# Nano_C1101_ds.net
KiCad netlist of a schematic drawn in EAGLE
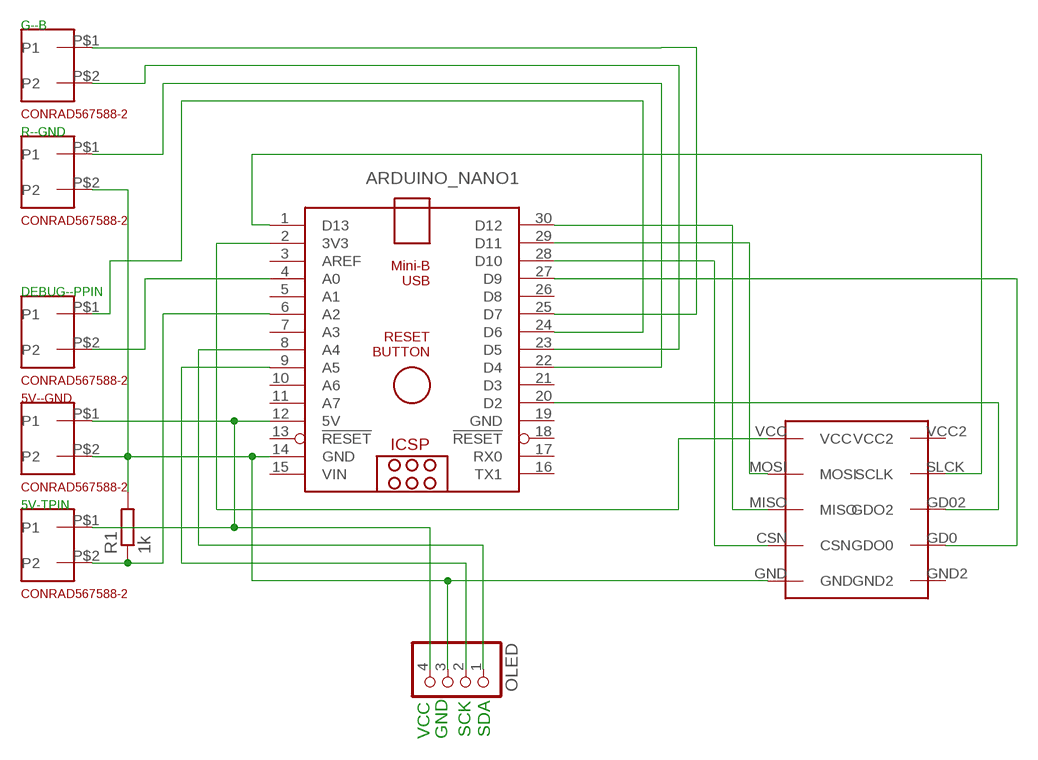
[diagram p0: schematic, sheet 1]

(export (version "E")
  (design (tool "Eeschema 10.0.6"))
  (components
    (comp (ref "5V--GND")
      (value "CONRAD567588-2")
      (footprint "eagle-import:CONRAD567588")
      (libsource (lib "eagle-import") (part "CONRAD567588-2"))
    )
    (comp (ref "5V-TPIN")
      (value "CONRAD567588-2")
      (footprint "eagle-import:CONRAD567588")
      (libsource (lib "eagle-import") (part "CONRAD567588-2"))
    )
    (comp (ref "ARDUINO_NANO1")
      (value "ARDUINO_NANO")
      (footprint "eagle-import:ARDUINO_NANO")
      (libsource (lib "eagle-import") (part "ARDUINO_NANO"))
    )
    (comp (ref "DEBUG--PPIN")
      (value "CONRAD567588-2")
      (footprint "eagle-import:CONRAD567588")
      (libsource (lib "eagle-import") (part "CONRAD567588-2"))
    )
    (comp (ref "G--B")
      (value "CONRAD567588-2")
      (footprint "eagle-import:CONRAD567588")
      (libsource (lib "eagle-import") (part "CONRAD567588-2"))
    )
    (comp (ref "OLED")
      (value "PINHD-1X4")
      (footprint "eagle-import:1X04")
      (libsource (lib "eagle-import") (part "PINHD-1X4"))
    )
    (comp (ref "R--GND")
      (value "CONRAD567588-2")
      (footprint "eagle-import:CONRAD567588")
      (libsource (lib "eagle-import") (part "CONRAD567588-2"))
    )
    (comp (ref "R1")
      (value "1k")
      (footprint "eagle-import:0204_7")
      (libsource (lib "eagle-import") (part "R-EU_0204/7"))
    )
    (comp (ref "U$1")
      (value "NEUFTECH_CC1101")
      (footprint "eagle-import:NEUFTECH_CC1101_PACKAGE_BOTTOM_VIEW")
      (libsource (lib "eagle-import") (part "NEUFTECH_CC1101"))
    )
  )
  (nets
    (net (code "1") (name "/GND") (class "Default")
      (node (ref "ARDUINO_NANO1") (pin "19") (pinfunction "GND_19") (pintype "power_in"))
    )
    (net (code "2") (name "/VIN") (class "Default")
      (node (ref "ARDUINO_NANO1") (pin "15") (pinfunction "VIN_15") (pintype "power_in"))
    )
    (net (code "3") (name "Net-(5V--GND-P1)") (class "Default")
      (node (ref "5V--GND") (pin "P$1") (pinfunction "P1_P$1") (pintype "bidirectional"))
      (node (ref "5V-TPIN") (pin "P$1") (pinfunction "P1_P$1") (pintype "bidirectional"))
      (node (ref "ARDUINO_NANO1") (pin "12") (pinfunction "5V_12") (pintype "power_in"))
      (node (ref "OLED") (pin "4") (pinfunction "4_4") (pintype "passive"))
    )
    (net (code "4") (name "Net-(5V--GND-P2)") (class "Default")
      (node (ref "5V--GND") (pin "P$2") (pinfunction "P2_P$2") (pintype "bidirectional"))
      (node (ref "ARDUINO_NANO1") (pin "14") (pinfunction "GND_14") (pintype "power_in"))
      (node (ref "OLED") (pin "3") (pinfunction "3_3") (pintype "passive"))
      (node (ref "R--GND") (pin "P$2") (pinfunction "P2_P$2") (pintype "bidirectional"))
      (node (ref "R1") (pin "2") (pinfunction "2_2") (pintype "passive"))
      (node (ref "U$1") (pin "GND") (pinfunction "GND_GND") (pintype "bidirectional"))
    )
    (net (code "5") (name "Net-(5V-TPIN-P2)") (class "Default")
      (node (ref "5V-TPIN") (pin "P$2") (pinfunction "P2_P$2") (pintype "bidirectional"))
      (node (ref "ARDUINO_NANO1") (pin "6") (pinfunction "A2_6") (pintype "bidirectional"))
      (node (ref "R1") (pin "1") (pinfunction "1_1") (pintype "passive"))
    )
    (net (code "6") (name "Net-(ARDUINO_NANO1-3V3)") (class "Default")
      (node (ref "ARDUINO_NANO1") (pin "2") (pinfunction "3V3_2") (pintype "output"))
      (node (ref "U$1") (pin "VCC") (pinfunction "VCC_VCC") (pintype "bidirectional"))
    )
    (net (code "7") (name "Net-(ARDUINO_NANO1-A0)") (class "Default")
      (node (ref "ARDUINO_NANO1") (pin "4") (pinfunction "A0_4") (pintype "bidirectional"))
      (node (ref "DEBUG--PPIN") (pin "P$2") (pinfunction "P2_P$2") (pintype "bidirectional"))
    )
    (net (code "8") (name "Net-(ARDUINO_NANO1-A4)") (class "Default")
      (node (ref "ARDUINO_NANO1") (pin "8") (pinfunction "A4_8") (pintype "bidirectional"))
      (node (ref "OLED") (pin "1") (pinfunction "1_1") (pintype "passive"))
    )
    (net (code "9") (name "Net-(ARDUINO_NANO1-A5)") (class "Default")
      (node (ref "ARDUINO_NANO1") (pin "9") (pinfunction "A5_9") (pintype "bidirectional"))
      (node (ref "OLED") (pin "2") (pinfunction "2_2") (pintype "passive"))
    )
    (net (code "10") (name "Net-(ARDUINO_NANO1-D2)") (class "Default")
      (node (ref "ARDUINO_NANO1") (pin "20") (pinfunction "D2_20") (pintype "bidirectional"))
      (node (ref "U$1") (pin "GD02") (pinfunction "GDO2_GD02") (pintype "bidirectional"))
    )
    (net (code "11") (name "Net-(ARDUINO_NANO1-D4)") (class "Default")
      (node (ref "ARDUINO_NANO1") (pin "22") (pinfunction "D4_22") (pintype "bidirectional"))
      (node (ref "R--GND") (pin "P$1") (pinfunction "P1_P$1") (pintype "bidirectional"))
    )
    (net (code "12") (name "Net-(ARDUINO_NANO1-D5)") (class "Default")
      (node (ref "ARDUINO_NANO1") (pin "23") (pinfunction "D5_23") (pintype "bidirectional"))
      (node (ref "G--B") (pin "P$2") (pinfunction "P2_P$2") (pintype "bidirectional"))
    )
    (net (code "13") (name "Net-(ARDUINO_NANO1-D6)") (class "Default")
      (node (ref "ARDUINO_NANO1") (pin "24") (pinfunction "D6_24") (pintype "bidirectional"))
      (node (ref "DEBUG--PPIN") (pin "P$1") (pinfunction "P1_P$1") (pintype "bidirectional"))
    )
    (net (code "14") (name "Net-(ARDUINO_NANO1-D7)") (class "Default")
      (node (ref "ARDUINO_NANO1") (pin "25") (pinfunction "D7_25") (pintype "bidirectional"))
      (node (ref "G--B") (pin "P$1") (pinfunction "P1_P$1") (pintype "bidirectional"))
    )
    (net (code "15") (name "Net-(ARDUINO_NANO1-D9)") (class "Default")
      (node (ref "ARDUINO_NANO1") (pin "27") (pinfunction "D9_27") (pintype "bidirectional"))
      (node (ref "U$1") (pin "GD0") (pinfunction "GDO0_GD0") (pintype "bidirectional"))
    )
    (net (code "16") (name "Net-(ARDUINO_NANO1-D10)") (class "Default")
      (node (ref "ARDUINO_NANO1") (pin "28") (pinfunction "D10_28") (pintype "bidirectional"))
      (node (ref "U$1") (pin "CSN") (pinfunction "CSN_CSN") (pintype "bidirectional"))
    )
    (net (code "17") (name "Net-(ARDUINO_NANO1-D11)") (class "Default")
      (node (ref "ARDUINO_NANO1") (pin "29") (pinfunction "D11_29") (pintype "bidirectional"))
      (node (ref "U$1") (pin "MOSI") (pinfunction "MOSI_MOSI") (pintype "bidirectional"))
    )
    (net (code "18") (name "Net-(ARDUINO_NANO1-D12)") (class "Default")
      (node (ref "ARDUINO_NANO1") (pin "30") (pinfunction "D12_30") (pintype "bidirectional"))
      (node (ref "U$1") (pin "MISO") (pinfunction "MISO_MISO") (pintype "bidirectional"))
    )
    (net (code "19") (name "Net-(ARDUINO_NANO1-D13)") (class "Default")
      (node (ref "ARDUINO_NANO1") (pin "1") (pinfunction "D13_1") (pintype "bidirectional"))
      (node (ref "U$1") (pin "SLCK") (pinfunction "SCLK_SLCK") (pintype "bidirectional"))
    )
    (net (code "20") (name "unconnected-(ARDUINO_NANO1-A1-Pad5)") (class "Default")
      (node (ref "ARDUINO_NANO1") (pin "5") (pinfunction "A1_5") (pintype "bidirectional"))
    )
    (net (code "21") (name "unconnected-(ARDUINO_NANO1-A3-Pad7)") (class "Default")
      (node (ref "ARDUINO_NANO1") (pin "7") (pinfunction "A3_7") (pintype "bidirectional"))
    )
    (net (code "22") (name "unconnected-(ARDUINO_NANO1-A6-Pad10)") (class "Default")
      (node (ref "ARDUINO_NANO1") (pin "10") (pinfunction "A6_10") (pintype "bidirectional"))
    )
    (net (code "23") (name "unconnected-(ARDUINO_NANO1-A7-Pad11)") (class "Default")
      (node (ref "ARDUINO_NANO1") (pin "11") (pinfunction "A7_11") (pintype "bidirectional"))
    )
    (net (code "24") (name "unconnected-(ARDUINO_NANO1-AREF-Pad3)") (class "Default")
      (node (ref "ARDUINO_NANO1") (pin "3") (pinfunction "AREF_3") (pintype "input"))
    )
    (net (code "25") (name "unconnected-(ARDUINO_NANO1-D3-Pad21)") (class "Default")
      (node (ref "ARDUINO_NANO1") (pin "21") (pinfunction "D3_21") (pintype "bidirectional"))
    )
    (net (code "26") (name "unconnected-(ARDUINO_NANO1-D8-Pad26)") (class "Default")
      (node (ref "ARDUINO_NANO1") (pin "26") (pinfunction "D8_26") (pintype "bidirectional"))
    )
    (net (code "27") (name "unconnected-(ARDUINO_NANO1-RX0-Pad17)") (class "Default")
      (node (ref "ARDUINO_NANO1") (pin "17") (pinfunction "RX0_17") (pintype "bidirectional"))
    )
    (net (code "28") (name "unconnected-(ARDUINO_NANO1-TX1-Pad16)") (class "Default")
      (node (ref "ARDUINO_NANO1") (pin "16") (pinfunction "TX1_16") (pintype "bidirectional"))
    )
    (net (code "29") (name "unconnected-(ARDUINO_NANO1-~{RESET}-Pad13)") (class "Default")
      (node (ref "ARDUINO_NANO1") (pin "13") (pinfunction "~{RESET}_13") (pintype "input"))
    )
    (net (code "30") (name "unconnected-(ARDUINO_NANO1-~{RESET}-Pad18)") (class "Default")
      (node (ref "ARDUINO_NANO1") (pin "18") (pinfunction "~{RESET}_18") (pintype "input"))
    )
    (net (code "31") (name "unconnected-(U$1-PadGND2)") (class "Default")
      (node (ref "U$1") (pin "GND2") (pinfunction "GND2_GND2") (pintype "bidirectional"))
    )
    (net (code "32") (name "unconnected-(U$1-PadVCC2)") (class "Default")
      (node (ref "U$1") (pin "VCC2") (pinfunction "VCC2_VCC2") (pintype "bidirectional"))
    )
  )
)
